# untitled.net
KiCad netlist of a schematic drawn in EAGLE
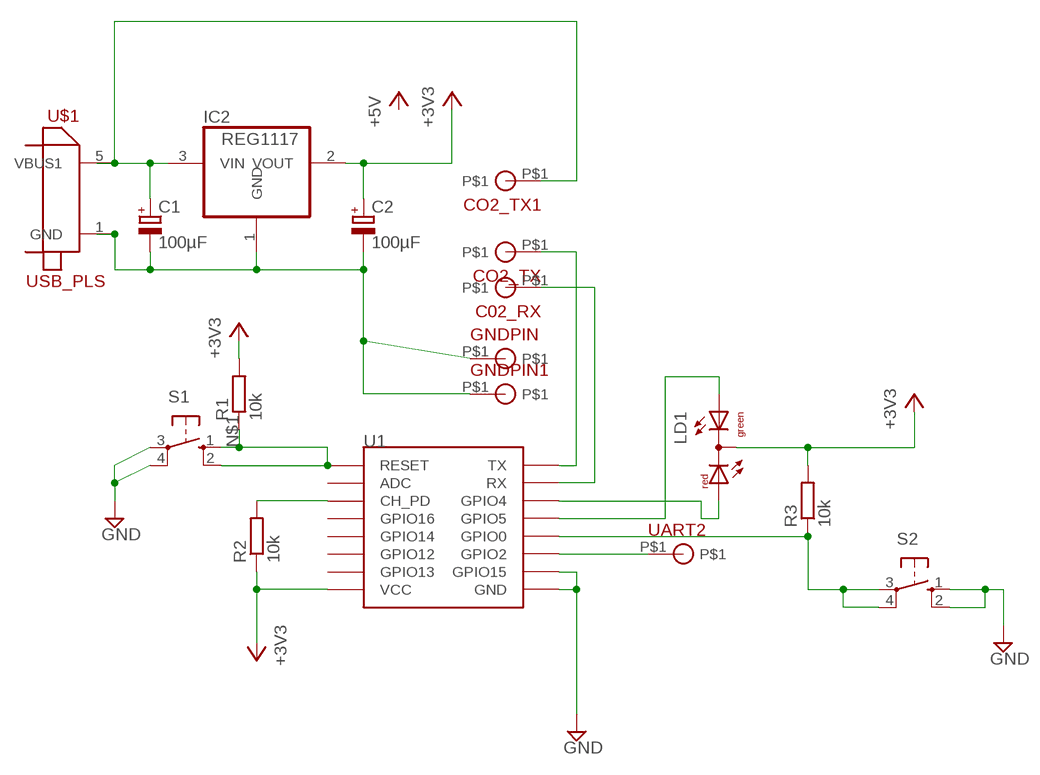
[diagram p0: schematic, sheet 1]

(export (version "E")
  (design (tool "Eeschema 10.0.6"))
  (components
    (comp (ref "C1")
      (value "100µF")
      (footprint "eagle-import:E5-6")
      (libsource (lib "eagle-import") (part "CPOL-EUE5-6"))
    )
    (comp (ref "C2")
      (value "100µF")
      (footprint "eagle-import:E5-6")
      (libsource (lib "eagle-import") (part "CPOL-EUE5-6"))
    )
    (comp (ref "C02_RX")
      (value "1PIN")
      (footprint "eagle-import:1PIN")
      (libsource (lib "eagle-import") (part "1PIN"))
    )
    (comp (ref "CO2_TX")
      (value "1PIN")
      (footprint "eagle-import:1PIN")
      (libsource (lib "eagle-import") (part "1PIN"))
    )
    (comp (ref "CO2_TX1")
      (value "1PIN")
      (footprint "eagle-import:1PIN")
      (libsource (lib "eagle-import") (part "1PIN"))
    )
    (comp (ref "GNDPIN")
      (value "1PIN")
      (footprint "eagle-import:1PIN")
      (libsource (lib "eagle-import") (part "1PIN"))
    )
    (comp (ref "GNDPIN1")
      (value "1PIN")
      (footprint "eagle-import:1PIN")
      (libsource (lib "eagle-import") (part "1PIN"))
    )
    (comp (ref "IC2")
      (value "REG1117")
      (footprint "eagle-import:SOT223")
      (libsource (lib "eagle-import") (part "REG1117"))
    )
    (comp (ref "LD1")
      (value "DUOLED-RG-C")
      (footprint "eagle-import:DUOLED-C-5MM")
      (libsource (lib "eagle-import") (part "DUOLED-RG-C"))
    )
    (comp (ref "R1")
      (value "10k")
      (footprint "eagle-import:R0603")
      (libsource (lib "eagle-import") (part "R-EU_R0603"))
    )
    (comp (ref "R2")
      (value "10k")
      (footprint "eagle-import:R0603")
      (libsource (lib "eagle-import") (part "R-EU_R0603"))
    )
    (comp (ref "R3")
      (value "10k")
      (footprint "eagle-import:R0603")
      (libsource (lib "eagle-import") (part "R-EU_R0603"))
    )
    (comp (ref "S1")
      (value "10-XX")
      (footprint "eagle-import:B3F-10XX")
      (fields (field (name "MPN") "B3F-1000"))
      (libsource (lib "eagle-import") (part "10-XX"))
    )
    (comp (ref "S2")
      (value "10-XX")
      (footprint "eagle-import:B3F-10XX")
      (fields (field (name "MPN") "B3F-1000"))
      (libsource (lib "eagle-import") (part "10-XX"))
    )
    (comp (ref "U$1")
      (value "USB_PLS")
      (footprint "eagle-import:USB_PLB")
      (libsource (lib "eagle-import") (part "USB_PLS"))
    )
    (comp (ref "U1")
      (value "ESP12")
      (footprint "eagle-import:ESP12")
      (libsource (lib "eagle-import") (part "ESP12"))
    )
    (comp (ref "UART2")
      (value "1PIN")
      (footprint "eagle-import:1PIN")
      (libsource (lib "eagle-import") (part "1PIN"))
    )
  )
  (nets
    (net (code "1") (name "+3V3") (class "Default")
      (node (ref "C2") (pin "+") (pinfunction "+_+") (pintype "passive"))
      (node (ref "IC2") (pin "2") (pinfunction "VOUT_2") (pintype "output"))
      (node (ref "LD1") (pin "C") (pinfunction "C_C") (pintype "passive"))
      (node (ref "R1") (pin "2") (pinfunction "2_2") (pintype "passive"))
      (node (ref "R2") (pin "1") (pinfunction "1_1") (pintype "passive"))
      (node (ref "R3") (pin "2") (pinfunction "2_2") (pintype "passive"))
      (node (ref "U1") (pin "VCC") (pinfunction "VCC_VCC") (pintype "bidirectional"))
    )
    (net (code "3") (name "/N$1") (class "Default")
      (node (ref "R1") (pin "1") (pinfunction "1_1") (pintype "passive"))
      (node (ref "S1") (pin "1") (pinfunction "S_1") (pintype "passive"))
      (node (ref "S1") (pin "2") (pinfunction "S1_2") (pintype "passive"))
      (node (ref "U1") (pin "RESET") (pinfunction "RESET_RESET") (pintype "bidirectional"))
    )
    (net (code "4") (name "GND") (class "Default")
      (node (ref "C1") (pin "-") (pinfunction "-_-") (pintype "passive"))
      (node (ref "C2") (pin "-") (pinfunction "-_-") (pintype "passive"))
      (node (ref "GNDPIN") (pin "P$1") (pinfunction "P$1_P$1") (pintype "bidirectional"))
      (node (ref "GNDPIN1") (pin "P$1") (pinfunction "P$1_P$1") (pintype "bidirectional"))
      (node (ref "IC2") (pin "1") (pinfunction "GND_1") (pintype "power_in"))
      (node (ref "S1") (pin "3") (pinfunction "P_3") (pintype "passive"))
      (node (ref "S1") (pin "4") (pinfunction "P1_4") (pintype "passive"))
      (node (ref "S2") (pin "1") (pinfunction "S_1") (pintype "passive"))
      (node (ref "S2") (pin "2") (pinfunction "S1_2") (pintype "passive"))
      (node (ref "U$1") (pin "1") (pinfunction "GND_1") (pintype "bidirectional"))
      (node (ref "U1") (pin "GND") (pinfunction "GND_GND") (pintype "bidirectional"))
      (node (ref "U1") (pin "GPIO15") (pinfunction "GPIO15_GPIO15") (pintype "bidirectional"))
    )
    (net (code "5") (name "Net-(C02_RX-PadP$1)") (class "Default")
      (node (ref "C02_RX") (pin "P$1") (pinfunction "P$1_P$1") (pintype "bidirectional"))
      (node (ref "U1") (pin "RX") (pinfunction "RX_RX") (pintype "bidirectional"))
    )
    (net (code "6") (name "Net-(CO2_TX-PadP$1)") (class "Default")
      (node (ref "CO2_TX") (pin "P$1") (pinfunction "P$1_P$1") (pintype "bidirectional"))
      (node (ref "U1") (pin "TX") (pinfunction "TX_TX") (pintype "bidirectional"))
    )
    (net (code "7") (name "Net-(IC2-VIN)") (class "Default")
      (node (ref "C1") (pin "+") (pinfunction "+_+") (pintype "passive"))
      (node (ref "CO2_TX1") (pin "P$1") (pinfunction "P$1_P$1") (pintype "bidirectional"))
      (node (ref "IC2") (pin "3") (pinfunction "VIN_3") (pintype "input"))
      (node (ref "U$1") (pin "5") (pinfunction "VBUS1_5") (pintype "bidirectional"))
    )
    (net (code "8") (name "Net-(LD1-AG)") (class "Default")
      (node (ref "LD1") (pin "AX") (pinfunction "AG_AX") (pintype "passive"))
      (node (ref "U1") (pin "GPIO5") (pinfunction "GPIO5_GPIO5") (pintype "bidirectional"))
    )
    (net (code "9") (name "Net-(LD1-PadAR)") (class "Default")
      (node (ref "LD1") (pin "AR") (pinfunction "AR_AR") (pintype "passive"))
      (node (ref "U1") (pin "GPIO4") (pinfunction "GPIO4_GPIO4") (pintype "bidirectional"))
    )
    (net (code "10") (name "Net-(R2-Pad2)") (class "Default")
      (node (ref "R2") (pin "2") (pinfunction "2_2") (pintype "passive"))
      (node (ref "U1") (pin "CH_PD") (pinfunction "CH_PD_CH_PD") (pintype "bidirectional"))
    )
    (net (code "11") (name "Net-(S2-P)") (class "Default")
      (node (ref "R3") (pin "1") (pinfunction "1_1") (pintype "passive"))
      (node (ref "S2") (pin "3") (pinfunction "P_3") (pintype "passive"))
      (node (ref "S2") (pin "4") (pinfunction "P1_4") (pintype "passive"))
      (node (ref "U1") (pin "GPIO0") (pinfunction "GPIO0_GPIO0") (pintype "bidirectional"))
    )
    (net (code "12") (name "Net-(U1-PadGPIO2)") (class "Default")
      (node (ref "U1") (pin "GPIO2") (pinfunction "GPIO2_GPIO2") (pintype "bidirectional"))
      (node (ref "UART2") (pin "P$1") (pinfunction "P$1_P$1") (pintype "bidirectional"))
    )
    (net (code "13") (name "unconnected-(U1-PadADC)") (class "Default")
      (node (ref "U1") (pin "ADC") (pinfunction "ADC_ADC") (pintype "bidirectional"))
    )
    (net (code "14") (name "unconnected-(U1-PadGPIO12)") (class "Default")
      (node (ref "U1") (pin "GPIO12") (pinfunction "GPIO12_GPIO12") (pintype "bidirectional"))
    )
    (net (code "15") (name "unconnected-(U1-PadGPIO13)") (class "Default")
      (node (ref "U1") (pin "GPIO13") (pinfunction "GPIO13_GPIO13") (pintype "bidirectional"))
    )
    (net (code "16") (name "unconnected-(U1-PadGPIO14)") (class "Default")
      (node (ref "U1") (pin "GPIO14") (pinfunction "GPIO14_GPIO14") (pintype "bidirectional"))
    )
    (net (code "17") (name "unconnected-(U1-PadGPIO16)") (class "Default")
      (node (ref "U1") (pin "GPIO16") (pinfunction "GPIO16_GPIO16") (pintype "bidirectional"))
    )
  )
)
